# BATT_CPU_TEST_BED_V2.net
KiCad netlist of a schematic drawn in EAGLE
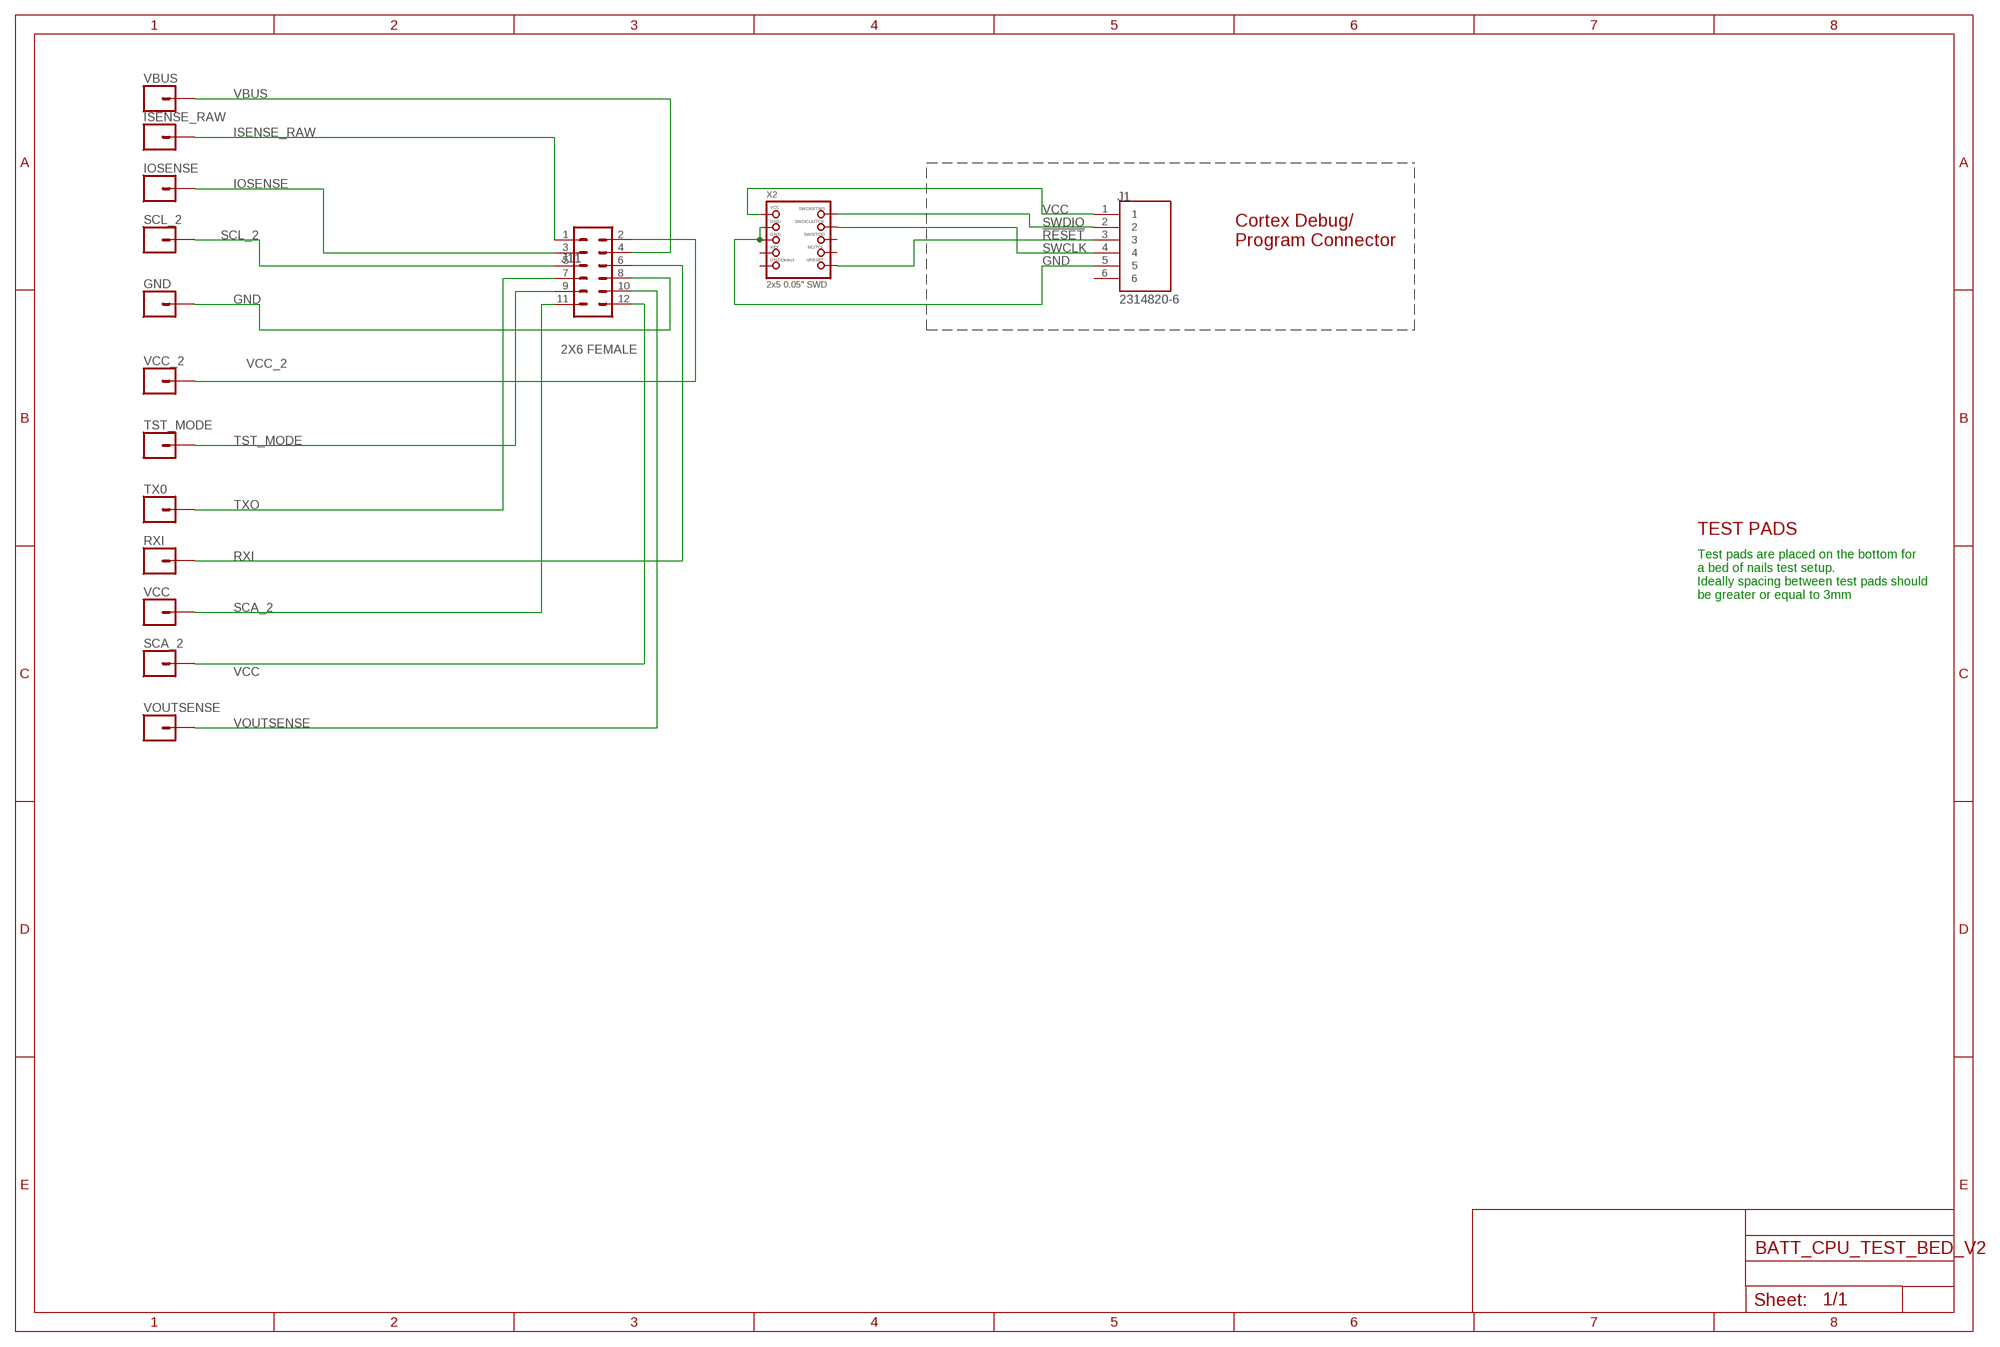
[diagram p0: schematic, sheet 1]

(export (version "E")
  (design (tool "Eeschema 10.0.6"))
  (components
    (comp (ref "GND")
      (value "CONN_01POGOPIN_HOLE_LARGE")
      (footprint "eagle-import:1X01_POGOPIN_HOLE_0.061_DIA")
      (libsource (lib "eagle-import") (part "CONN_01POGOPIN_HOLE_LARGE"))
    )
    (comp (ref "IOSENSE")
      (value "CONN_01POGOPIN_HOLE_LARGE")
      (footprint "eagle-import:1X01_POGOPIN_HOLE_0.061_DIA")
      (libsource (lib "eagle-import") (part "CONN_01POGOPIN_HOLE_LARGE"))
    )
    (comp (ref "ISENSE_RAW")
      (value "CONN_01POGOPIN_HOLE_LARGE")
      (footprint "eagle-import:1X01_POGOPIN_HOLE_0.061_DIA")
      (libsource (lib "eagle-import") (part "CONN_01POGOPIN_HOLE_LARGE"))
    )
    (comp (ref "J1")
      (value "2314820-6")
      (footprint "eagle-import:TE_2314820-6")
      (fields (field (name "DIGI-KEY_PART_NUMBER") "17-2314820-6-ND") (field (name "MF") "TE Connectivity"))
      (libsource (lib "eagle-import") (part "2314820-6"))
    )
    (comp (ref "J11")
      (value "2X6 FEMALE")
      (footprint "eagle-import:2X6")
      (libsource (lib "eagle-import") (part "CONN_06X2PTH_FEMALE"))
    )
    (comp (ref "RXI")
      (value "CONN_01POGOPIN_HOLE_LARGE")
      (footprint "eagle-import:1X01_POGOPIN_HOLE_0.061_DIA")
      (libsource (lib "eagle-import") (part "CONN_01POGOPIN_HOLE_LARGE"))
    )
    (comp (ref "SCA_2")
      (value "CONN_01POGOPIN_HOLE_LARGE")
      (footprint "eagle-import:1X01_POGOPIN_HOLE_0.061_DIA")
      (libsource (lib "eagle-import") (part "CONN_01POGOPIN_HOLE_LARGE"))
    )
    (comp (ref "SCL_2")
      (value "CONN_01POGOPIN_HOLE_LARGE")
      (footprint "eagle-import:1X01_POGOPIN_HOLE_0.061_DIA")
      (libsource (lib "eagle-import") (part "CONN_01POGOPIN_HOLE_LARGE"))
    )
    (comp (ref "TST_MODE")
      (value "CONN_01POGOPIN_HOLE_LARGE")
      (footprint "eagle-import:1X01_POGOPIN_HOLE_0.061_DIA")
      (libsource (lib "eagle-import") (part "CONN_01POGOPIN_HOLE_LARGE"))
    )
    (comp (ref "TX0")
      (value "CONN_01POGOPIN_HOLE_LARGE")
      (footprint "eagle-import:1X01_POGOPIN_HOLE_0.061_DIA")
      (libsource (lib "eagle-import") (part "CONN_01POGOPIN_HOLE_LARGE"))
    )
    (comp (ref "VBUS")
      (value "CONN_01POGOPIN_HOLE_LARGE")
      (footprint "eagle-import:1X01_POGOPIN_HOLE_0.061_DIA")
      (libsource (lib "eagle-import") (part "CONN_01POGOPIN_HOLE_LARGE"))
    )
    (comp (ref "VCC")
      (value "CONN_01POGOPIN_HOLE_LARGE")
      (footprint "eagle-import:1X01_POGOPIN_HOLE_0.061_DIA")
      (libsource (lib "eagle-import") (part "CONN_01POGOPIN_HOLE_LARGE"))
    )
    (comp (ref "VCC_2")
      (value "CONN_01POGOPIN_HOLE_LARGE")
      (footprint "eagle-import:1X01_POGOPIN_HOLE_0.061_DIA")
      (libsource (lib "eagle-import") (part "CONN_01POGOPIN_HOLE_LARGE"))
    )
    (comp (ref "VOUTSENSE")
      (value "CONN_01POGOPIN_HOLE_LARGE")
      (footprint "eagle-import:1X01_POGOPIN_HOLE_0.061_DIA")
      (libsource (lib "eagle-import") (part "CONN_01POGOPIN_HOLE_LARGE"))
    )
    (comp (ref "X2")
      (value "2x5 0.05\" SWD")
      (footprint "eagle-import:2X05_1.27MM_BOX_POSTS")
      (libsource (lib "eagle-import") (part "JTAG-CORTEXBOXPOSTS"))
    )
  )
  (nets
    (net (code "1") (name "/GND") (class "Default")
      (node (ref "GND") (pin "2") (pinfunction "1_2") (pintype "passive"))
      (node (ref "J1") (pin "5") (pinfunction "5_5") (pintype "passive"))
      (node (ref "J11") (pin "8") (pinfunction "8_8") (pintype "passive"))
      (node (ref "X2") (pin "3") (pinfunction "GND_3") (pintype "power_in"))
      (node (ref "X2") (pin "5") (pinfunction "GND_5") (pintype "power_in"))
    )
    (net (code "2") (name "/IOSENSE") (class "Default")
      (node (ref "IOSENSE") (pin "2") (pinfunction "1_2") (pintype "passive"))
      (node (ref "J11") (pin "3") (pinfunction "3_3") (pintype "passive"))
    )
    (net (code "3") (name "/ISENSE_RAW") (class "Default")
      (node (ref "ISENSE_RAW") (pin "2") (pinfunction "1_2") (pintype "passive"))
      (node (ref "J11") (pin "1") (pinfunction "1_1") (pintype "passive"))
    )
    (net (code "4") (name "/RXI") (class "Default")
      (node (ref "J11") (pin "6") (pinfunction "6_6") (pintype "passive"))
      (node (ref "RXI") (pin "2") (pinfunction "1_2") (pintype "passive"))
    )
    (net (code "5") (name "/SCA_2") (class "Default")
      (node (ref "J11") (pin "12") (pinfunction "12_12") (pintype "passive"))
      (node (ref "SCA_2") (pin "2") (pinfunction "1_2") (pintype "passive"))
    )
    (net (code "6") (name "/SCL_2") (class "Default")
      (node (ref "J11") (pin "5") (pinfunction "5_5") (pintype "passive"))
      (node (ref "SCL_2") (pin "2") (pinfunction "1_2") (pintype "passive"))
    )
    (net (code "7") (name "/SWCLK") (class "Default")
      (node (ref "J1") (pin "4") (pinfunction "4_4") (pintype "passive"))
      (node (ref "X2") (pin "4") (pinfunction "SWDCLK_4") (pintype "bidirectional"))
    )
    (net (code "8") (name "/SWDIO") (class "Default")
      (node (ref "J1") (pin "2") (pinfunction "2_2") (pintype "passive"))
      (node (ref "X2") (pin "2") (pinfunction "SWDIO_2") (pintype "bidirectional"))
    )
    (net (code "9") (name "/TST_MODE") (class "Default")
      (node (ref "J11") (pin "9") (pinfunction "9_9") (pintype "passive"))
      (node (ref "TST_MODE") (pin "2") (pinfunction "1_2") (pintype "passive"))
    )
    (net (code "10") (name "/TXO") (class "Default")
      (node (ref "J11") (pin "7") (pinfunction "7_7") (pintype "passive"))
      (node (ref "TX0") (pin "2") (pinfunction "1_2") (pintype "passive"))
    )
    (net (code "11") (name "/VBUS") (class "Default")
      (node (ref "J11") (pin "4") (pinfunction "4_4") (pintype "passive"))
      (node (ref "VBUS") (pin "2") (pinfunction "1_2") (pintype "passive"))
    )
    (net (code "12") (name "/VCC") (class "Default")
      (node (ref "J1") (pin "1") (pinfunction "1_1") (pintype "passive"))
      (node (ref "J11") (pin "11") (pinfunction "11_11") (pintype "passive"))
      (node (ref "VCC") (pin "2") (pinfunction "1_2") (pintype "passive"))
      (node (ref "X2") (pin "1") (pinfunction "VCC_1") (pintype "power_in"))
    )
    (net (code "13") (name "/VCC_2") (class "Default")
      (node (ref "J11") (pin "2") (pinfunction "2_2") (pintype "passive"))
      (node (ref "VCC_2") (pin "2") (pinfunction "1_2") (pintype "passive"))
    )
    (net (code "14") (name "/VOUTSENSE") (class "Default")
      (node (ref "J11") (pin "10") (pinfunction "10_10") (pintype "passive"))
      (node (ref "VOUTSENSE") (pin "2") (pinfunction "1_2") (pintype "passive"))
    )
    (net (code "15") (name "/~{RESET}") (class "Default")
      (node (ref "J1") (pin "3") (pinfunction "3_3") (pintype "passive"))
      (node (ref "X2") (pin "10") (pinfunction "NRESET_10") (pintype "bidirectional"))
    )
    (net (code "16") (name "unconnected-(J1-Pad6)") (class "Default")
      (node (ref "J1") (pin "6") (pinfunction "6_6") (pintype "passive"))
    )
    (net (code "17") (name "unconnected-(X2-GNDDETECT-Pad9)") (class "Default")
      (node (ref "X2") (pin "9") (pinfunction "GNDDETECT_9") (pintype "bidirectional"))
    )
    (net (code "18") (name "unconnected-(X2-KEY-Pad7)") (class "Default")
      (node (ref "X2") (pin "7") (pinfunction "KEY_7") (pintype "bidirectional"))
    )
    (net (code "19") (name "unconnected-(X2-SWO-Pad6)") (class "Default")
      (node (ref "X2") (pin "6") (pinfunction "SWO_6") (pintype "bidirectional"))
    )
    (net (code "20") (name "unconnected-(X2-TDI-Pad8)") (class "Default")
      (node (ref "X2") (pin "8") (pinfunction "TDI_8") (pintype "bidirectional"))
    )
  )
)
